# trezor_v1_0.net
KiCad netlist of a schematic drawn in EAGLE
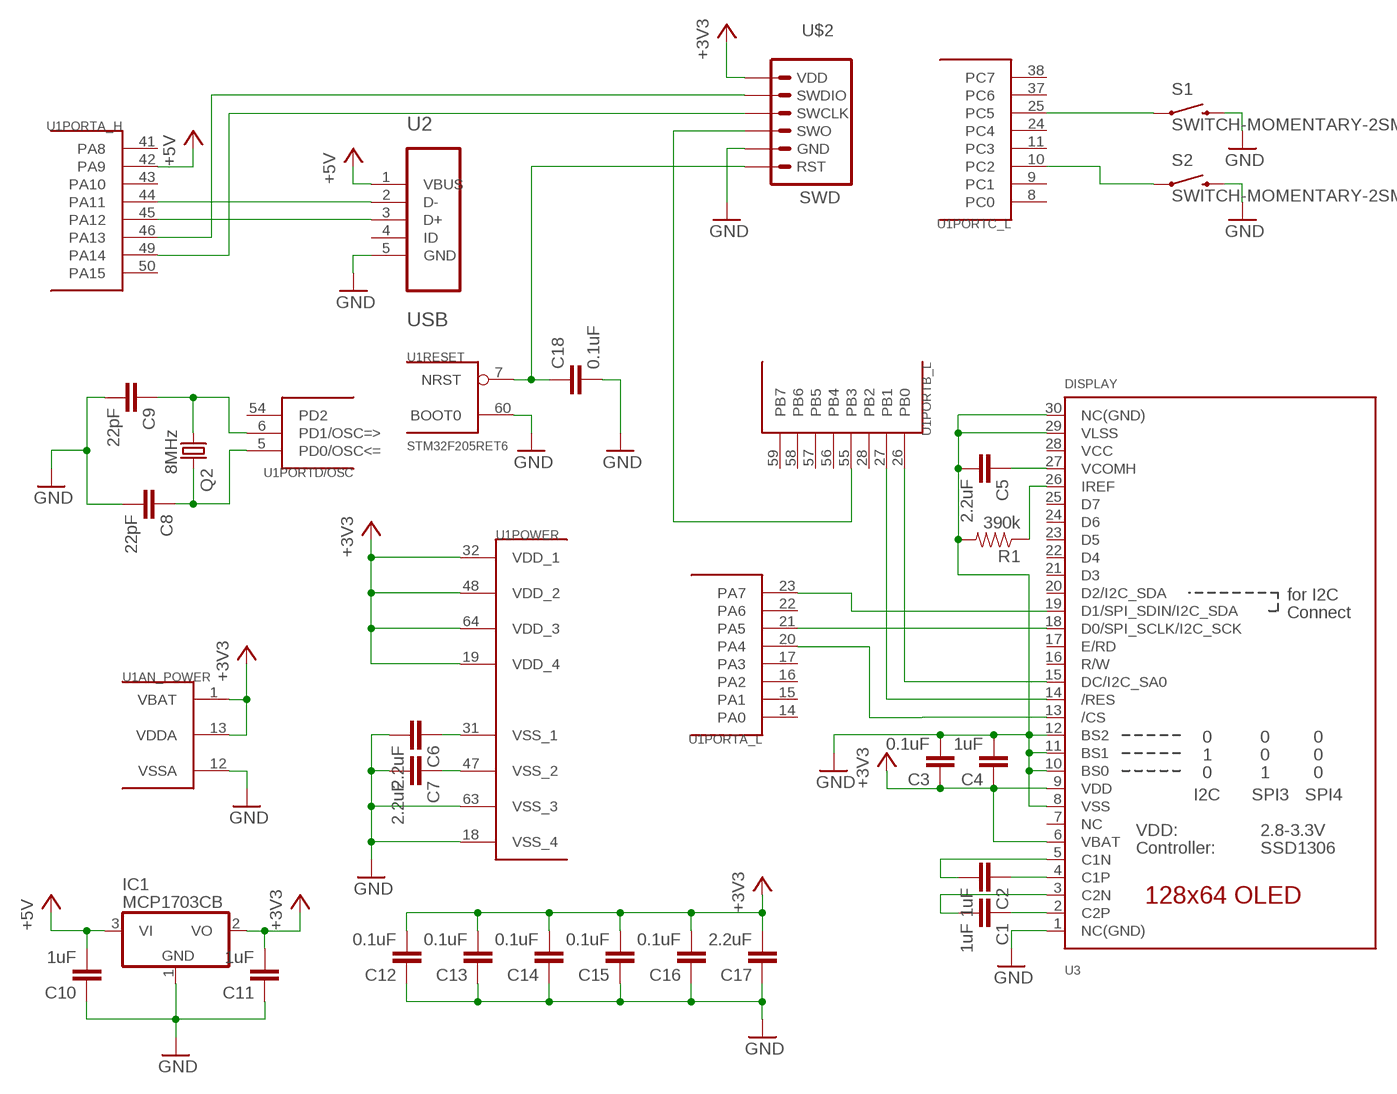
[diagram p0: schematic, sheet 1]

(export (version "E")
  (design (tool "Eeschema 10.0.6"))
  (components
    (comp (ref "C1")
      (value "1uF")
      (footprint "eagle-import:0603-CAP")
      (libsource (lib "eagle-import") (part "CAP0603-CAP"))
    )
    (comp (ref "C2")
      (value "1uF")
      (footprint "eagle-import:0603-CAP")
      (libsource (lib "eagle-import") (part "CAP0603-CAP"))
    )
    (comp (ref "C3")
      (value "0.1uF")
      (footprint "eagle-import:0603-CAP")
      (libsource (lib "eagle-import") (part "CAP0603-CAP"))
    )
    (comp (ref "C4")
      (value "1uF")
      (footprint "eagle-import:0603-CAP")
      (libsource (lib "eagle-import") (part "CAP0603-CAP"))
    )
    (comp (ref "C5")
      (value "2.2uF")
      (footprint "eagle-import:0603-CAP")
      (libsource (lib "eagle-import") (part "CAP0603-CAP"))
    )
    (comp (ref "C6")
      (value "2.2uF")
      (footprint "eagle-import:0603-CAP")
      (libsource (lib "eagle-import") (part "CAP0603-CAP"))
    )
    (comp (ref "C7")
      (value "2.2uF")
      (footprint "eagle-import:0603-CAP")
      (libsource (lib "eagle-import") (part "CAP0603-CAP"))
    )
    (comp (ref "C8")
      (value "22pF")
      (footprint "eagle-import:0603-CAP")
      (libsource (lib "eagle-import") (part "CAP0603-CAP"))
    )
    (comp (ref "C9")
      (value "22pF")
      (footprint "eagle-import:0603-CAP")
      (libsource (lib "eagle-import") (part "CAP0603-CAP"))
    )
    (comp (ref "C10")
      (value "1uF")
      (footprint "eagle-import:0603-CAP")
      (libsource (lib "eagle-import") (part "CAP0603-CAP"))
    )
    (comp (ref "C11")
      (value "1uF")
      (footprint "eagle-import:0603-CAP")
      (libsource (lib "eagle-import") (part "CAP0603-CAP"))
    )
    (comp (ref "C12")
      (value "0.1uF")
      (footprint "eagle-import:0603-CAP")
      (libsource (lib "eagle-import") (part "CAP0603-CAP"))
    )
    (comp (ref "C13")
      (value "0.1uF")
      (footprint "eagle-import:0603-CAP")
      (libsource (lib "eagle-import") (part "CAP0603-CAP"))
    )
    (comp (ref "C14")
      (value "0.1uF")
      (footprint "eagle-import:0603-CAP")
      (libsource (lib "eagle-import") (part "CAP0603-CAP"))
    )
    (comp (ref "C15")
      (value "0.1uF")
      (footprint "eagle-import:0603-CAP")
      (libsource (lib "eagle-import") (part "CAP0603-CAP"))
    )
    (comp (ref "C16")
      (value "0.1uF")
      (footprint "eagle-import:0603-CAP")
      (libsource (lib "eagle-import") (part "CAP0603-CAP"))
    )
    (comp (ref "C17")
      (value "2.2uF")
      (footprint "eagle-import:0603-CAP")
      (libsource (lib "eagle-import") (part "CAP0603-CAP"))
    )
    (comp (ref "C18")
      (value "0.1uF")
      (footprint "eagle-import:0603-CAP")
      (libsource (lib "eagle-import") (part "CAP0603-CAP"))
    )
    (comp (ref "IC1")
      (value "MCP1703CB")
      (footprint "eagle-import:SOT23")
      (libsource (lib "eagle-import") (part "MCP1703CB"))
    )
    (comp (ref "Q2")
      (value "8MHz")
      (footprint "eagle-import:CTS406")
      (libsource (lib "eagle-import") (part "CRYSTALCTS406"))
    )
    (comp (ref "R1")
      (value "390k")
      (footprint "eagle-import:0603-RES")
      (libsource (lib "eagle-import") (part "RESISTOR0603-RES"))
    )
    (comp (ref "S1")
      (value "SWITCH-MOMENTARY-2SMD")
      (footprint "eagle-import:TACTILE_SWITCH_SMD")
      (libsource (lib "eagle-import") (part "SWITCH-MOMENTARY-2SMD"))
    )
    (comp (ref "S2")
      (value "SWITCH-MOMENTARY-2SMD")
      (footprint "eagle-import:TACTILE_SWITCH_SMD")
      (libsource (lib "eagle-import") (part "SWITCH-MOMENTARY-2SMD"))
    )
    (comp (ref "U$2")
      (value "SWD")
      (footprint "eagle-import:SWD")
      (libsource (lib "eagle-import") (part "SWD"))
    )
    (comp (ref "U1")
      (value "STM32F205RET6")
      (footprint "eagle-import:TQFP64")
      (libsource (lib "eagle-import") (part "STM32F10XRXT6"))
    )
    (comp (ref "U2")
      (value "USB")
      (footprint "eagle-import:MOLEX_47346-0001")
      (fields (field (name "MPN") "47346-0001"))
      (libsource (lib "eagle-import") (part "47346-0001"))
    )
    (comp (ref "U3")
      (value "DISPLAY")
      (footprint "eagle-import:UG-2864HSWEG01_0.96IN_WRAPAROUND")
      (libsource (lib "eagle-import") (part "DISP_OLED_UG-2864HSWEG010.96{dblquote}"))
    )
  )
  (nets
    (net (code "1") (name "+3V3") (class "Default")
      (node (ref "C11") (pin "2") (pinfunction "2_2") (pintype "passive"))
      (node (ref "C12") (pin "2") (pinfunction "2_2") (pintype "passive"))
      (node (ref "C13") (pin "2") (pinfunction "2_2") (pintype "passive"))
      (node (ref "C14") (pin "2") (pinfunction "2_2") (pintype "passive"))
      (node (ref "C15") (pin "2") (pinfunction "2_2") (pintype "passive"))
      (node (ref "C16") (pin "2") (pinfunction "2_2") (pintype "passive"))
      (node (ref "C17") (pin "2") (pinfunction "2_2") (pintype "passive"))
      (node (ref "C3") (pin "1") (pinfunction "1_1") (pintype "passive"))
      (node (ref "C4") (pin "1") (pinfunction "1_1") (pintype "passive"))
      (node (ref "IC1") (pin "2") (pinfunction "VO_2") (pintype "passive"))
      (node (ref "U$2") (pin "6") (pinfunction "VDD_6") (pintype "passive"))
      (node (ref "U1") (pin "1") (pinfunction "VBAT_1") (pintype "power_in"))
      (node (ref "U1") (pin "13") (pinfunction "VDDA_13") (pintype "power_in"))
      (node (ref "U1") (pin "19") (pinfunction "VDD_4_19") (pintype "power_in"))
      (node (ref "U1") (pin "32") (pinfunction "VDD_1_32") (pintype "power_in"))
      (node (ref "U1") (pin "48") (pinfunction "VDD_2_48") (pintype "power_in"))
      (node (ref "U1") (pin "64") (pinfunction "VDD_3_64") (pintype "power_in"))
      (node (ref "U3") (pin "6") (pinfunction "VBAT_6") (pintype "input"))
      (node (ref "U3") (pin "9") (pinfunction "VDD_9") (pintype "power_in"))
    )
    (net (code "2") (name "+5V") (class "Default")
      (node (ref "C10") (pin "2") (pinfunction "2_2") (pintype "passive"))
      (node (ref "IC1") (pin "3") (pinfunction "VI_3") (pintype "input"))
      (node (ref "U1") (pin "42") (pinfunction "PA9_42") (pintype "bidirectional"))
      (node (ref "U2") (pin "1") (pinfunction "VBUS_1") (pintype "input"))
    )
    (net (code "3") (name "/VCC") (class "Default")
      (node (ref "U3") (pin "28") (pinfunction "VCC_28") (pintype "power_in"))
    )
    (net (code "4") (name "GND") (class "Default")
      (node (ref "C10") (pin "1") (pinfunction "1_1") (pintype "passive"))
      (node (ref "C11") (pin "1") (pinfunction "1_1") (pintype "passive"))
      (node (ref "C12") (pin "1") (pinfunction "1_1") (pintype "passive"))
      (node (ref "C13") (pin "1") (pinfunction "1_1") (pintype "passive"))
      (node (ref "C14") (pin "1") (pinfunction "1_1") (pintype "passive"))
      (node (ref "C15") (pin "1") (pinfunction "1_1") (pintype "passive"))
      (node (ref "C16") (pin "1") (pinfunction "1_1") (pintype "passive"))
      (node (ref "C17") (pin "1") (pinfunction "1_1") (pintype "passive"))
      (node (ref "C18") (pin "2") (pinfunction "2_2") (pintype "passive"))
      (node (ref "C3") (pin "2") (pinfunction "2_2") (pintype "passive"))
      (node (ref "C4") (pin "2") (pinfunction "2_2") (pintype "passive"))
      (node (ref "C5") (pin "2") (pinfunction "2_2") (pintype "passive"))
      (node (ref "C6") (pin "2") (pinfunction "2_2") (pintype "passive"))
      (node (ref "C7") (pin "2") (pinfunction "2_2") (pintype "passive"))
      (node (ref "C8") (pin "2") (pinfunction "2_2") (pintype "passive"))
      (node (ref "C9") (pin "2") (pinfunction "2_2") (pintype "passive"))
      (node (ref "IC1") (pin "1") (pinfunction "GND_1") (pintype "passive"))
      (node (ref "R1") (pin "2") (pinfunction "2_2") (pintype "passive"))
      (node (ref "S1") (pin "3") (pinfunction "2_3") (pintype "passive"))
      (node (ref "S2") (pin "3") (pinfunction "2_3") (pintype "passive"))
      (node (ref "U$2") (pin "2") (pinfunction "GND_2") (pintype "passive"))
      (node (ref "U1") (pin "12") (pinfunction "VSSA_12") (pintype "power_in"))
      (node (ref "U1") (pin "18") (pinfunction "VSS_4_18") (pintype "power_in"))
      (node (ref "U1") (pin "60") (pinfunction "BOOT0_60") (pintype "input"))
      (node (ref "U1") (pin "63") (pinfunction "VSS_3_63") (pintype "power_in"))
      (node (ref "U2") (pin "5") (pinfunction "GND_5") (pintype "input"))
      (node (ref "U3") (pin "1") (pinfunction "NC(GND)_1") (pintype "input"))
      (node (ref "U3") (pin "10") (pinfunction "BS0_10") (pintype "input"))
      (node (ref "U3") (pin "11") (pinfunction "BS1_11") (pintype "input"))
      (node (ref "U3") (pin "12") (pinfunction "BS2_12") (pintype "input"))
      (node (ref "U3") (pin "29") (pinfunction "VLSS_29") (pintype "power_in"))
      (node (ref "U3") (pin "30") (pinfunction "NC(GND)_30") (pintype "input"))
      (node (ref "U3") (pin "8") (pinfunction "VSS_8") (pintype "power_in"))
    )
    (net (code "5") (name "Net-(Q2-2)") (class "Default")
      (node (ref "C8") (pin "1") (pinfunction "1_1") (pintype "passive"))
      (node (ref "Q2") (pin "3") (pinfunction "2_3") (pintype "passive"))
      (node (ref "U1") (pin "5") (pinfunction "PD0/OSC<=_5") (pintype "bidirectional"))
    )
    (net (code "6") (name "Net-(U$2-RST)") (class "Default")
      (node (ref "C18") (pin "1") (pinfunction "1_1") (pintype "passive"))
      (node (ref "U$2") (pin "1") (pinfunction "RST_1") (pintype "passive"))
      (node (ref "U1") (pin "7") (pinfunction "NRST_7") (pintype "input"))
    )
    (net (code "7") (name "Net-(U$2-SWCLK)") (class "Default")
      (node (ref "U$2") (pin "4") (pinfunction "SWCLK_4") (pintype "passive"))
      (node (ref "U1") (pin "49") (pinfunction "PA14_49") (pintype "bidirectional"))
    )
    (net (code "8") (name "Net-(U$2-SWDIO)") (class "Default")
      (node (ref "U$2") (pin "5") (pinfunction "SWDIO_5") (pintype "passive"))
      (node (ref "U1") (pin "46") (pinfunction "PA13_46") (pintype "bidirectional"))
    )
    (net (code "9") (name "Net-(U$2-SWO)") (class "Default")
      (node (ref "U$2") (pin "3") (pinfunction "SWO_3") (pintype "passive"))
      (node (ref "U1") (pin "55") (pinfunction "PB3_55") (pintype "bidirectional"))
    )
    (net (code "10") (name "Net-(U1B-PA11)") (class "Default")
      (node (ref "U1") (pin "44") (pinfunction "PA11_44") (pintype "bidirectional"))
      (node (ref "U2") (pin "2") (pinfunction "D-_2") (pintype "input"))
    )
    (net (code "11") (name "Net-(U1B-PA12)") (class "Default")
      (node (ref "U1") (pin "45") (pinfunction "PA12_45") (pintype "bidirectional"))
      (node (ref "U2") (pin "3") (pinfunction "D+_3") (pintype "input"))
    )
    (net (code "12") (name "Net-(U1C-PA4)") (class "Default")
      (node (ref "U1") (pin "20") (pinfunction "PA4_20") (pintype "bidirectional"))
      (node (ref "U3") (pin "13") (pinfunction "/CS_13") (pintype "input"))
    )
    (net (code "13") (name "Net-(U1C-PA5)") (class "Default")
      (node (ref "U1") (pin "21") (pinfunction "PA5_21") (pintype "bidirectional"))
      (node (ref "U3") (pin "18") (pinfunction "D0/SPI_SCLK/I2C_SCK_18") (pintype "bidirectional"))
    )
    (net (code "14") (name "Net-(U1C-PA7)") (class "Default")
      (node (ref "U1") (pin "23") (pinfunction "PA7_23") (pintype "bidirectional"))
      (node (ref "U3") (pin "19") (pinfunction "D1/SPI_SDIN/I2C_SDA_19") (pintype "bidirectional"))
    )
    (net (code "15") (name "Net-(U1E-PB0)") (class "Default")
      (node (ref "U1") (pin "26") (pinfunction "PB0_26") (pintype "bidirectional"))
      (node (ref "U3") (pin "15") (pinfunction "DC/I2C_SA0_15") (pintype "input"))
    )
    (net (code "16") (name "Net-(U1E-PB1)") (class "Default")
      (node (ref "U1") (pin "27") (pinfunction "PB1_27") (pintype "bidirectional"))
      (node (ref "U3") (pin "14") (pinfunction "/RES_14") (pintype "input"))
    )
    (net (code "17") (name "Net-(U1G-PC2)") (class "Default")
      (node (ref "S2") (pin "1") (pinfunction "1_1") (pintype "passive"))
      (node (ref "U1") (pin "10") (pinfunction "PC2_10") (pintype "bidirectional"))
    )
    (net (code "18") (name "Net-(U1G-PC5)") (class "Default")
      (node (ref "S1") (pin "1") (pinfunction "1_1") (pintype "passive"))
      (node (ref "U1") (pin "25") (pinfunction "PC5_25") (pintype "bidirectional"))
    )
    (net (code "19") (name "Net-(U1H-PD1{slash}OSC=>)") (class "Default")
      (node (ref "C9") (pin "1") (pinfunction "1_1") (pintype "passive"))
      (node (ref "Q2") (pin "1") (pinfunction "1_1") (pintype "passive"))
      (node (ref "U1") (pin "6") (pinfunction "PD1/OSC=>_6") (pintype "bidirectional"))
    )
    (net (code "20") (name "Net-(U1I-VSS_1)") (class "Default")
      (node (ref "C6") (pin "1") (pinfunction "1_1") (pintype "passive"))
      (node (ref "U1") (pin "31") (pinfunction "VSS_1_31") (pintype "power_in"))
    )
    (net (code "21") (name "Net-(U1I-VSS_2)") (class "Default")
      (node (ref "C7") (pin "1") (pinfunction "1_1") (pintype "passive"))
      (node (ref "U1") (pin "47") (pinfunction "VSS_2_47") (pintype "power_in"))
    )
    (net (code "22") (name "Net-(U3-C1N)") (class "Default")
      (node (ref "C2") (pin "2") (pinfunction "2_2") (pintype "passive"))
      (node (ref "U3") (pin "5") (pinfunction "C1N_5") (pintype "input"))
    )
    (net (code "23") (name "Net-(U3-C1P)") (class "Default")
      (node (ref "C2") (pin "1") (pinfunction "1_1") (pintype "passive"))
      (node (ref "U3") (pin "4") (pinfunction "C1P_4") (pintype "input"))
    )
    (net (code "24") (name "Net-(U3-C2N)") (class "Default")
      (node (ref "C1") (pin "2") (pinfunction "2_2") (pintype "passive"))
      (node (ref "U3") (pin "3") (pinfunction "C2N_3") (pintype "input"))
    )
    (net (code "25") (name "Net-(U3-C2P)") (class "Default")
      (node (ref "C1") (pin "1") (pinfunction "1_1") (pintype "passive"))
      (node (ref "U3") (pin "2") (pinfunction "C2P_2") (pintype "input"))
    )
    (net (code "26") (name "Net-(U3-IREF)") (class "Default")
      (node (ref "R1") (pin "1") (pinfunction "1_1") (pintype "passive"))
      (node (ref "U3") (pin "26") (pinfunction "IREF_26") (pintype "input"))
    )
    (net (code "27") (name "Net-(U3-VCOMH)") (class "Default")
      (node (ref "C5") (pin "1") (pinfunction "1_1") (pintype "passive"))
      (node (ref "U3") (pin "27") (pinfunction "VCOMH_27") (pintype "output"))
    )
    (net (code "28") (name "unconnected-(U1B-PA8-Pad41)") (class "Default")
      (node (ref "U1") (pin "41") (pinfunction "PA8_41") (pintype "bidirectional"))
    )
    (net (code "29") (name "unconnected-(U1B-PA10-Pad43)") (class "Default")
      (node (ref "U1") (pin "43") (pinfunction "PA10_43") (pintype "bidirectional"))
    )
    (net (code "30") (name "unconnected-(U1B-PA15-Pad50)") (class "Default")
      (node (ref "U1") (pin "50") (pinfunction "PA15_50") (pintype "bidirectional"))
    )
    (net (code "31") (name "unconnected-(U1C-PA0-Pad14)") (class "Default")
      (node (ref "U1") (pin "14") (pinfunction "PA0_14") (pintype "bidirectional"))
    )
    (net (code "32") (name "unconnected-(U1C-PA1-Pad15)") (class "Default")
      (node (ref "U1") (pin "15") (pinfunction "PA1_15") (pintype "bidirectional"))
    )
    (net (code "33") (name "unconnected-(U1C-PA2-Pad16)") (class "Default")
      (node (ref "U1") (pin "16") (pinfunction "PA2_16") (pintype "bidirectional"))
    )
    (net (code "34") (name "unconnected-(U1C-PA3-Pad17)") (class "Default")
      (node (ref "U1") (pin "17") (pinfunction "PA3_17") (pintype "bidirectional"))
    )
    (net (code "35") (name "unconnected-(U1C-PA6-Pad22)") (class "Default")
      (node (ref "U1") (pin "22") (pinfunction "PA6_22") (pintype "bidirectional"))
    )
    (net (code "36") (name "unconnected-(U1E-PB2-Pad28)") (class "Default")
      (node (ref "U1") (pin "28") (pinfunction "PB2_28") (pintype "bidirectional"))
    )
    (net (code "37") (name "unconnected-(U1E-PB4-Pad56)") (class "Default")
      (node (ref "U1") (pin "56") (pinfunction "PB4_56") (pintype "bidirectional"))
    )
    (net (code "38") (name "unconnected-(U1E-PB5-Pad57)") (class "Default")
      (node (ref "U1") (pin "57") (pinfunction "PB5_57") (pintype "bidirectional"))
    )
    (net (code "39") (name "unconnected-(U1E-PB6-Pad58)") (class "Default")
      (node (ref "U1") (pin "58") (pinfunction "PB6_58") (pintype "bidirectional"))
    )
    (net (code "40") (name "unconnected-(U1E-PB7-Pad59)") (class "Default")
      (node (ref "U1") (pin "59") (pinfunction "PB7_59") (pintype "bidirectional"))
    )
    (net (code "41") (name "unconnected-(U1G-PC0-Pad8)") (class "Default")
      (node (ref "U1") (pin "8") (pinfunction "PC0_8") (pintype "bidirectional"))
    )
    (net (code "42") (name "unconnected-(U1G-PC1-Pad9)") (class "Default")
      (node (ref "U1") (pin "9") (pinfunction "PC1_9") (pintype "bidirectional"))
    )
    (net (code "43") (name "unconnected-(U1G-PC3-Pad11)") (class "Default")
      (node (ref "U1") (pin "11") (pinfunction "PC3_11") (pintype "bidirectional"))
    )
    (net (code "44") (name "unconnected-(U1G-PC4-Pad24)") (class "Default")
      (node (ref "U1") (pin "24") (pinfunction "PC4_24") (pintype "bidirectional"))
    )
    (net (code "45") (name "unconnected-(U1G-PC6-Pad37)") (class "Default")
      (node (ref "U1") (pin "37") (pinfunction "PC6_37") (pintype "bidirectional"))
    )
    (net (code "46") (name "unconnected-(U1G-PC7-Pad38)") (class "Default")
      (node (ref "U1") (pin "38") (pinfunction "PC7_38") (pintype "bidirectional"))
    )
    (net (code "47") (name "unconnected-(U1H-PD2-Pad54)") (class "Default")
      (node (ref "U1") (pin "54") (pinfunction "PD2_54") (pintype "bidirectional"))
    )
    (net (code "48") (name "unconnected-(U2-ID-Pad4)") (class "Default")
      (node (ref "U2") (pin "4") (pinfunction "ID_4") (pintype "input"))
    )
    (net (code "49") (name "unconnected-(U3-D2{slash}I2C_SDA-Pad20)") (class "Default")
      (node (ref "U3") (pin "20") (pinfunction "D2/I2C_SDA_20") (pintype "bidirectional"))
    )
    (net (code "50") (name "unconnected-(U3-D3-Pad21)") (class "Default")
      (node (ref "U3") (pin "21") (pinfunction "D3_21") (pintype "bidirectional"))
    )
    (net (code "51") (name "unconnected-(U3-D4-Pad22)") (class "Default")
      (node (ref "U3") (pin "22") (pinfunction "D4_22") (pintype "bidirectional"))
    )
    (net (code "52") (name "unconnected-(U3-D5-Pad23)") (class "Default")
      (node (ref "U3") (pin "23") (pinfunction "D5_23") (pintype "bidirectional"))
    )
    (net (code "53") (name "unconnected-(U3-D6-Pad24)") (class "Default")
      (node (ref "U3") (pin "24") (pinfunction "D6_24") (pintype "bidirectional"))
    )
    (net (code "54") (name "unconnected-(U3-D7-Pad25)") (class "Default")
      (node (ref "U3") (pin "25") (pinfunction "D7_25") (pintype "bidirectional"))
    )
    (net (code "55") (name "unconnected-(U3-E{slash}RD-Pad17)") (class "Default")
      (node (ref "U3") (pin "17") (pinfunction "E/RD_17") (pintype "input"))
    )
    (net (code "56") (name "unconnected-(U3-NC-Pad7)") (class "Default")
      (node (ref "U3") (pin "7") (pinfunction "NC_7") (pintype "no_connect"))
    )
    (net (code "57") (name "unconnected-(U3-R{slash}W-Pad16)") (class "Default")
      (node (ref "U3") (pin "16") (pinfunction "R/W_16") (pintype "input"))
    )
  )
)
